# Solar_Tracker_2.net
KiCad netlist of a schematic drawn in Altium Designer
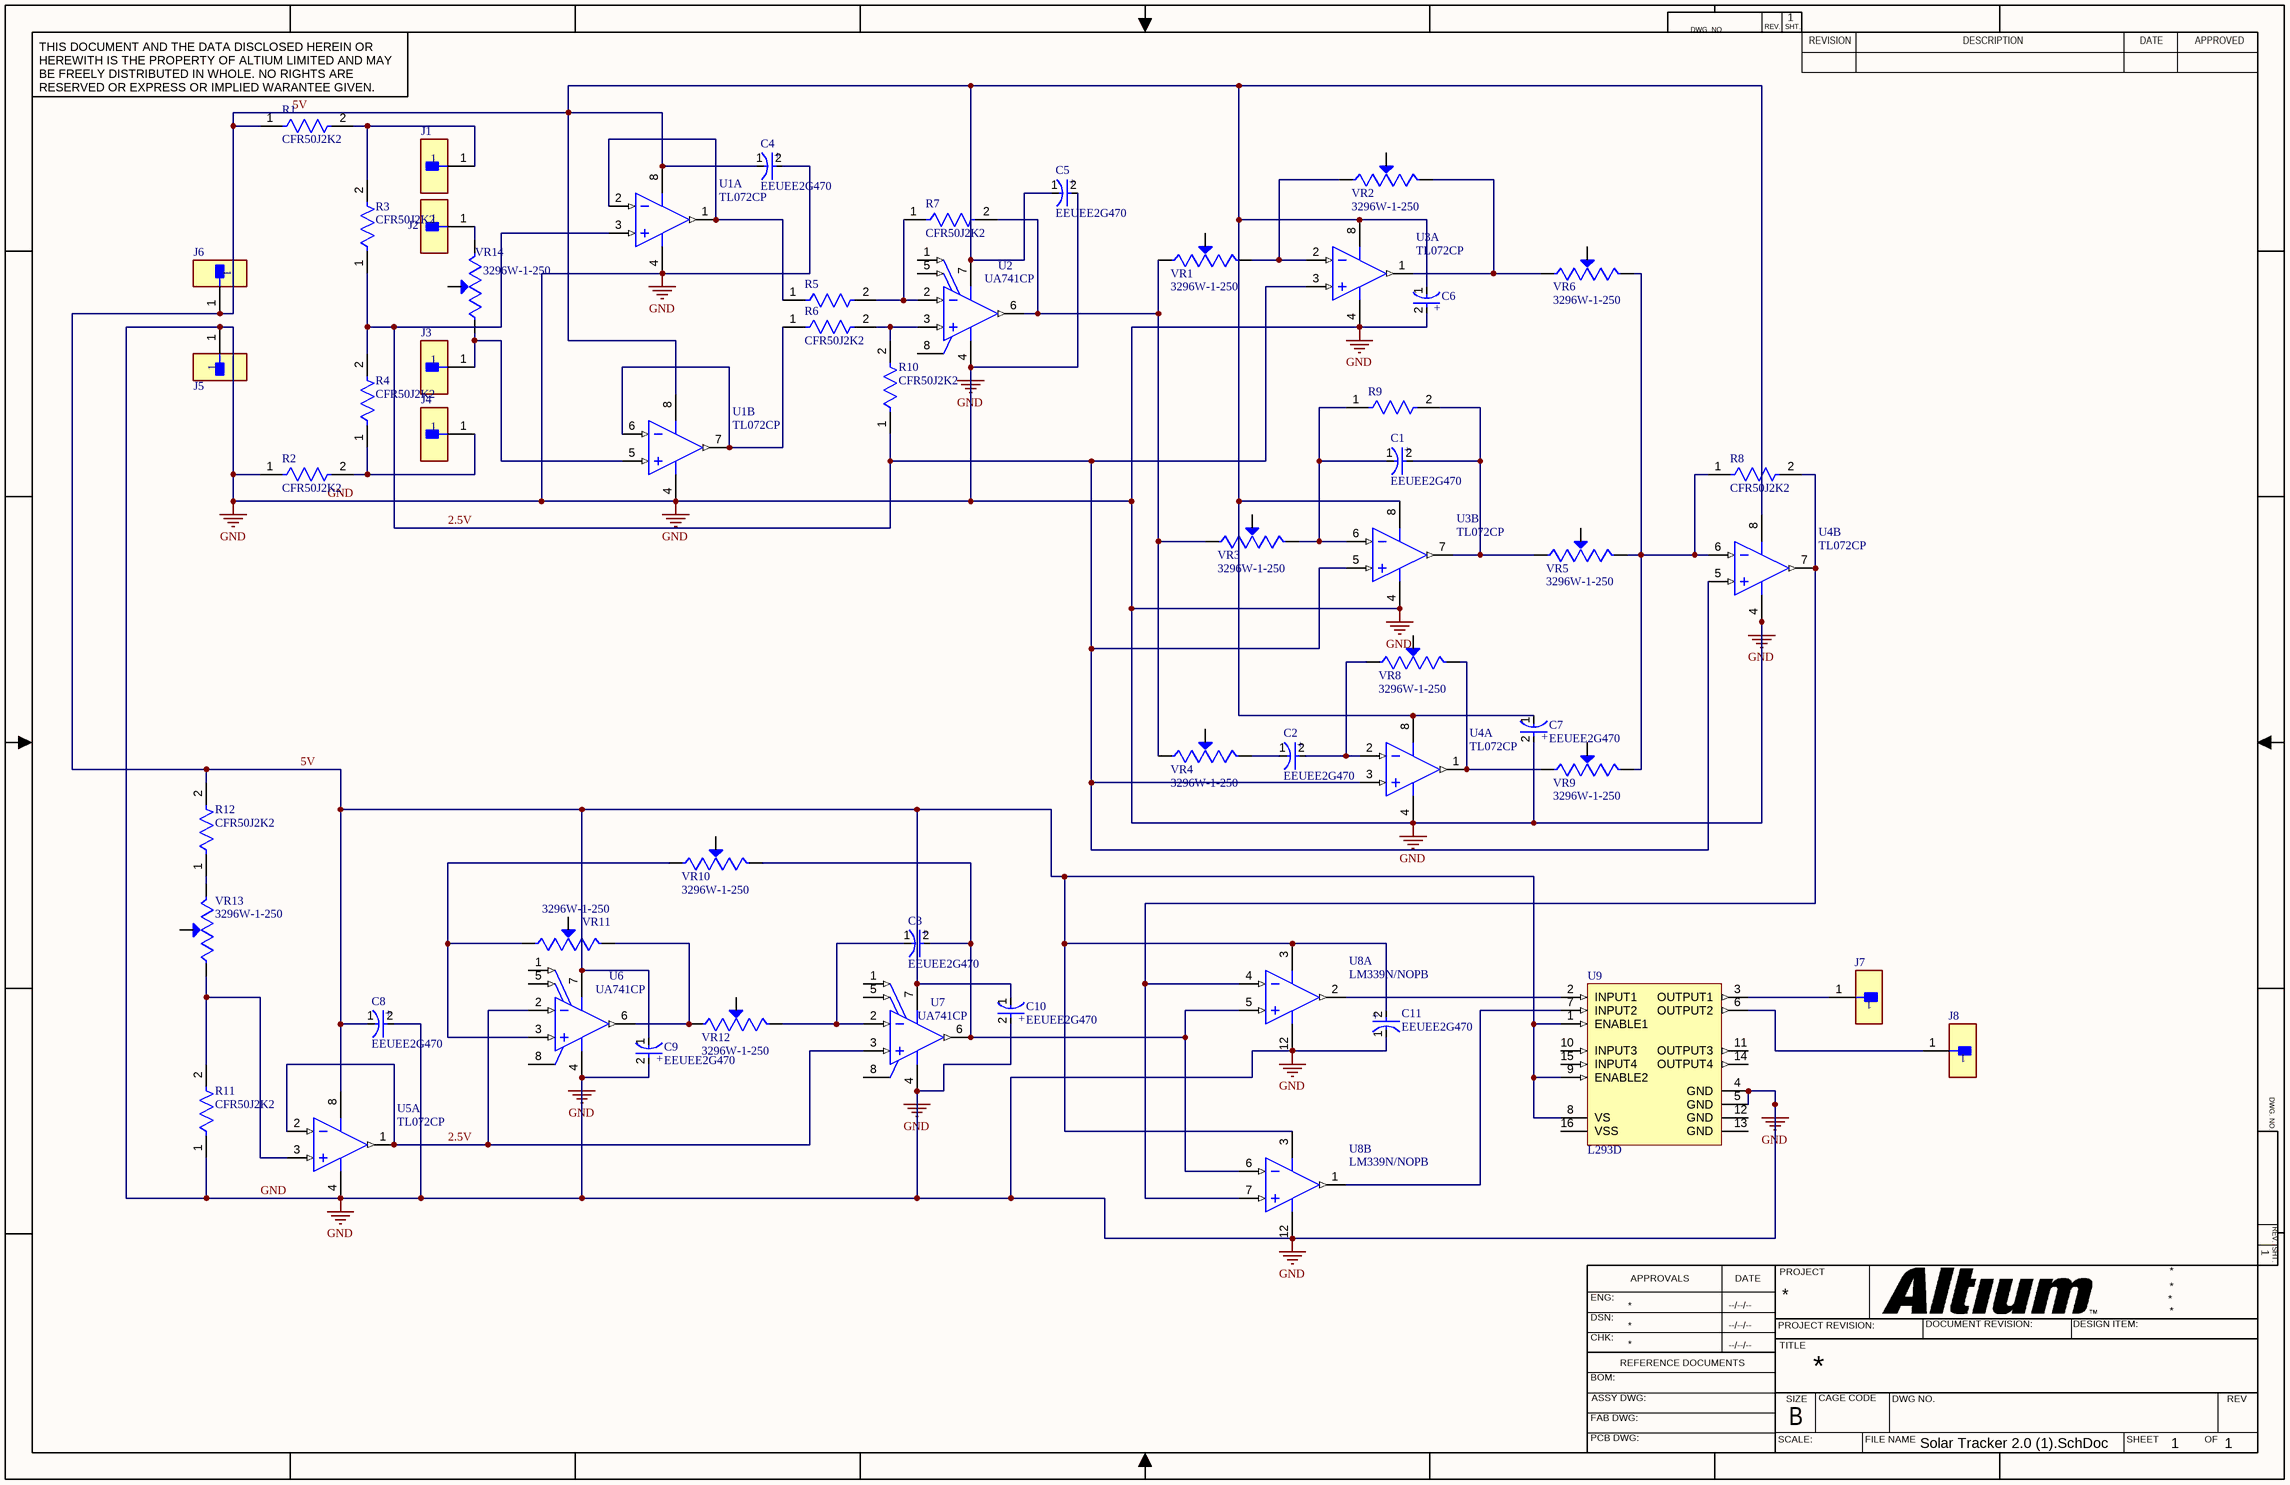
[diagram p0: Solar Tracker 2.0 (1).SchDoc]

(export (version "E")
  (design (tool "Eeschema 10.0.6"))
  (components
    (comp (ref "C1")
      (value "EEUEE2G470")
      (footprint "FP-RAD-TH-D_16_0_5-L_25_2-MFG")
      (description "Aluminum Electrolytic Capacitors (Radial Lead Type) 47uF ±20% 400V")
      (fields (field (name "VOLTAGE") "400V") (field (name "TOLERANCE") "20%"))
      (libsource (lib "Altium Content Vault") (part "203bc49f2ac43e59fd269a8c329ed05"))
    )
    (comp (ref "C2")
      (value "EEUEE2G470")
      (footprint "FP-RAD-TH-D_16_0_5-L_25_2-MFG")
      (description "Aluminum Electrolytic Capacitors (Radial Lead Type) 47uF ±20% 400V")
      (fields (field (name "VOLTAGE") "400V") (field (name "TOLERANCE") "20%"))
      (libsource (lib "Altium Content Vault") (part "203bc49f2ac43e59fd269a8c329ed05"))
    )
    (comp (ref "C3")
      (value "EEUEE2G470")
      (footprint "FP-RAD-TH-D_16_0_5-L_25_2-MFG")
      (description "Aluminum Electrolytic Capacitors (Radial Lead Type) 47uF ±20% 400V")
      (fields (field (name "VOLTAGE") "400V") (field (name "TOLERANCE") "20%"))
      (libsource (lib "Altium Content Vault") (part "203bc49f2ac43e59fd269a8c329ed05"))
    )
    (comp (ref "C4")
      (value "EEUEE2G470")
      (footprint "FP-RAD-TH-D_16_0_5-L_25_2-MFG")
      (description "Aluminum Electrolytic Capacitors (Radial Lead Type) 47uF ±20% 400V")
      (fields (field (name "VOLTAGE") "400V") (field (name "TOLERANCE") "20%"))
      (libsource (lib "Altium Content Vault") (part "203bc49f2ac43e59fd269a8c329ed05"))
    )
    (comp (ref "C5")
      (value "EEUEE2G470")
      (footprint "FP-RAD-TH-D_16_0_5-L_25_2-MFG")
      (description "Aluminum Electrolytic Capacitors (Radial Lead Type) 47uF ±20% 400V")
      (fields (field (name "VOLTAGE") "400V") (field (name "TOLERANCE") "20%"))
      (libsource (lib "Altium Content Vault") (part "203bc49f2ac43e59fd269a8c329ed05"))
    )
    (comp (ref "C6")
      (value "EEUEE2G470")
      (footprint "FP-RAD-TH-D_16_0_5-L_25_2-MFG")
      (description "Aluminum Electrolytic Capacitors (Radial Lead Type) 47uF ±20% 400V")
      (fields (field (name "VOLTAGE") "400V") (field (name "TOLERANCE") "20%"))
      (libsource (lib "Altium Content Vault") (part "203bc49f2ac43e59fd269a8c329ed05"))
    )
    (comp (ref "C7")
      (value "EEUEE2G470")
      (footprint "FP-RAD-TH-D_16_0_5-L_25_2-MFG")
      (description "Aluminum Electrolytic Capacitors (Radial Lead Type) 47uF ±20% 400V")
      (fields (field (name "VOLTAGE") "400V") (field (name "TOLERANCE") "20%"))
      (libsource (lib "Altium Content Vault") (part "203bc49f2ac43e59fd269a8c329ed05"))
    )
    (comp (ref "C8")
      (value "EEUEE2G470")
      (footprint "FP-RAD-TH-D_16_0_5-L_25_2-MFG")
      (description "Aluminum Electrolytic Capacitors (Radial Lead Type) 47uF ±20% 400V")
      (fields (field (name "VOLTAGE") "400V") (field (name "TOLERANCE") "20%"))
      (libsource (lib "Altium Content Vault") (part "203bc49f2ac43e59fd269a8c329ed05"))
    )
    (comp (ref "C9")
      (value "EEUEE2G470")
      (footprint "FP-RAD-TH-D_16_0_5-L_25_2-MFG")
      (description "Aluminum Electrolytic Capacitors (Radial Lead Type) 47uF ±20% 400V")
      (fields (field (name "VOLTAGE") "400V") (field (name "TOLERANCE") "20%"))
      (libsource (lib "Altium Content Vault") (part "203bc49f2ac43e59fd269a8c329ed05"))
    )
    (comp (ref "C10")
      (value "EEUEE2G470")
      (footprint "FP-RAD-TH-D_16_0_5-L_25_2-MFG")
      (description "Aluminum Electrolytic Capacitors (Radial Lead Type) 47uF ±20% 400V")
      (fields (field (name "VOLTAGE") "400V") (field (name "TOLERANCE") "20%"))
      (libsource (lib "Altium Content Vault") (part "203bc49f2ac43e59fd269a8c329ed05"))
    )
    (comp (ref "C11")
      (value "EEUEE2G470")
      (footprint "FP-RAD-TH-D_16_0_5-L_25_2-MFG")
      (description "Aluminum Electrolytic Capacitors (Radial Lead Type) 47uF ±20% 400V")
      (fields (field (name "VOLTAGE") "400V") (field (name "TOLERANCE") "20%"))
      (libsource (lib "Altium Content Vault") (part "203bc49f2ac43e59fd269a8c329ed05"))
    )
    (comp (ref "J1")
      (value "PBC01SAAN")
      (footprint "FP-PBC01SAAN-MFG")
      (description "CONN HEADER VERT 1POS")
      (libsource (lib "") (part "dd45045ce8184df9e99e12baf3f412c_2"))
    )
    (comp (ref "J2")
      (value "PBC01SAAN")
      (footprint "FP-PBC01SAAN-MFG")
      (description "CONN HEADER VERT 1POS")
      (libsource (lib "") (part "dd45045ce8184df9e99e12baf3f412c_2"))
    )
    (comp (ref "J3")
      (value "PBC01SAAN")
      (footprint "FP-PBC01SAAN-MFG")
      (description "CONN HEADER VERT 1POS")
      (libsource (lib "") (part "dd45045ce8184df9e99e12baf3f412c_2"))
    )
    (comp (ref "J4")
      (value "PBC01SAAN")
      (footprint "FP-PBC01SAAN-MFG")
      (description "CONN HEADER VERT 1POS")
      (libsource (lib "") (part "dd45045ce8184df9e99e12baf3f412c_2"))
    )
    (comp (ref "J5")
      (value "PBC01SAAN")
      (footprint "FP-PBC01SAAN-MFG")
      (description "CONN HEADER VERT 1POS")
      (libsource (lib "") (part "dd45045ce8184df9e99e12baf3f412c_1"))
    )
    (comp (ref "J6")
      (value "PBC01SAAN")
      (footprint "FP-PBC01SAAN-MFG")
      (description "CONN HEADER VERT 1POS")
      (libsource (lib "Altium Content Vault") (part "dd45045ce8184df9e99e12baf3f412c"))
    )
    (comp (ref "J7")
      (value "PBC01SAAN")
      (footprint "FP-PBC01SAAN-MFG")
      (description "CONN HEADER VERT 1POS")
      (libsource (lib "") (part "dd45045ce8184df9e99e12baf3f412c_3"))
    )
    (comp (ref "J8")
      (value "PBC01SAAN")
      (footprint "FP-PBC01SAAN-MFG")
      (description "CONN HEADER VERT 1POS")
      (libsource (lib "") (part "dd45045ce8184df9e99e12baf3f412c_3"))
    )
    (comp (ref "R1")
      (value "CFR50J2K2")
      (footprint "FP-CFR50J2K2-MFG")
      (description "RES 2.2K OHM 5% 1/2W AXIAL")
      (fields (field (name "TOLERANCE") "5%"))
      (libsource (lib "Altium Content Vault") (part "1029c3af85768c4190bb7ad29bc67b5"))
    )
    (comp (ref "R2")
      (value "CFR50J2K2")
      (footprint "FP-CFR50J2K2-MFG")
      (description "RES 2.2K OHM 5% 1/2W AXIAL")
      (fields (field (name "TOLERANCE") "5%"))
      (libsource (lib "Altium Content Vault") (part "1029c3af85768c4190bb7ad29bc67b5"))
    )
    (comp (ref "R3")
      (value "CFR50J2K2")
      (footprint "FP-CFR50J2K2-MFG")
      (description "RES 2.2K OHM 5% 1/2W AXIAL")
      (fields (field (name "TOLERANCE") "5%"))
      (libsource (lib "Altium Content Vault") (part "1029c3af85768c4190bb7ad29bc67b5"))
    )
    (comp (ref "R4")
      (value "CFR50J2K2")
      (footprint "FP-CFR50J2K2-MFG")
      (description "RES 2.2K OHM 5% 1/2W AXIAL")
      (fields (field (name "TOLERANCE") "5%"))
      (libsource (lib "Altium Content Vault") (part "1029c3af85768c4190bb7ad29bc67b5"))
    )
    (comp (ref "R5")
      (value "CFR50J2K2")
      (footprint "FP-CFR50J2K2-MFG")
      (description "RES 2.2K OHM 5% 1/2W AXIAL")
      (fields (field (name "TOLERANCE") "5%"))
      (libsource (lib "Altium Content Vault") (part "1029c3af85768c4190bb7ad29bc67b5"))
    )
    (comp (ref "R6")
      (value "CFR50J2K2")
      (footprint "FP-CFR50J2K2-MFG")
      (description "RES 2.2K OHM 5% 1/2W AXIAL")
      (fields (field (name "TOLERANCE") "5%"))
      (libsource (lib "Altium Content Vault") (part "1029c3af85768c4190bb7ad29bc67b5"))
    )
    (comp (ref "R7")
      (value "CFR50J2K2")
      (footprint "FP-CFR50J2K2-MFG")
      (description "RES 2.2K OHM 5% 1/2W AXIAL")
      (fields (field (name "TOLERANCE") "5%"))
      (libsource (lib "Altium Content Vault") (part "1029c3af85768c4190bb7ad29bc67b5"))
    )
    (comp (ref "R8")
      (value "CFR50J2K2")
      (footprint "FP-CFR50J2K2-MFG")
      (description "RES 2.2K OHM 5% 1/2W AXIAL")
      (fields (field (name "TOLERANCE") "5%"))
      (libsource (lib "Altium Content Vault") (part "1029c3af85768c4190bb7ad29bc67b5"))
    )
    (comp (ref "R9")
      (value "CFR50J2K2")
      (footprint "FP-CFR50J2K2-MFG")
      (description "RES 2.2K OHM 5% 1/2W AXIAL")
      (fields (field (name "TOLERANCE") "5%"))
      (libsource (lib "Altium Content Vault") (part "1029c3af85768c4190bb7ad29bc67b5"))
    )
    (comp (ref "R10")
      (value "CFR50J2K2")
      (footprint "FP-CFR50J2K2-MFG")
      (description "RES 2.2K OHM 5% 1/2W AXIAL")
      (fields (field (name "TOLERANCE") "5%"))
      (libsource (lib "Altium Content Vault") (part "1029c3af85768c4190bb7ad29bc67b5"))
    )
    (comp (ref "R11")
      (value "CFR50J2K2")
      (footprint "FP-CFR50J2K2-MFG")
      (description "RES 2.2K OHM 5% 1/2W AXIAL")
      (fields (field (name "TOLERANCE") "5%"))
      (libsource (lib "Altium Content Vault") (part "1029c3af85768c4190bb7ad29bc67b5"))
    )
    (comp (ref "R12")
      (value "CFR50J2K2")
      (footprint "FP-CFR50J2K2-MFG")
      (description "RES 2.2K OHM 5% 1/2W AXIAL")
      (fields (field (name "TOLERANCE") "5%"))
      (libsource (lib "Altium Content Vault") (part "1029c3af85768c4190bb7ad29bc67b5"))
    )
    (comp (ref "U1")
      (value "TL072CP")
      (footprint "P0008A")
      (fields (field (name "MANUFACTURER") "Texas Instruments"))
      (libsource (lib "Altium Content Vault") (part "TI-AMP-D6-2-8_D"))
    )
    (comp (ref "U2")
      (value "UA741CP")
      (footprint "P0008A")
      (description "General-Purpose Operational Amplifier, 7 to 36 V, 0 to 70 degC, 8-pin DIP (P8), Pb-Free (RoHS)")
      (fields (field (name "MANUFACTURER") "Texas Instruments"))
      (libsource (lib "Altium Content Vault") (part "TI-AMP-S5-2-8"))
    )
    (comp (ref "U3")
      (value "TL072CP")
      (footprint "P0008A")
      (fields (field (name "MANUFACTURER") "Texas Instruments"))
      (libsource (lib "Altium Content Vault") (part "TI-AMP-D6-2-8_D"))
    )
    (comp (ref "U4")
      (value "TL072CP")
      (footprint "P0008A")
      (fields (field (name "MANUFACTURER") "Texas Instruments"))
      (libsource (lib "Altium Content Vault") (part "TI-AMP-D6-2-8_D"))
    )
    (comp (ref "U5")
      (value "TL072CP")
      (footprint "P0008A")
      (fields (field (name "MANUFACTURER") "Texas Instruments"))
      (libsource (lib "Altium Content Vault") (part "TI-AMP-D6-2-8_D"))
    )
    (comp (ref "U6")
      (value "UA741CP")
      (footprint "P0008A")
      (description "General-Purpose Operational Amplifier, 7 to 36 V, 0 to 70 degC, 8-pin DIP (P8), Pb-Free (RoHS)")
      (fields (field (name "MANUFACTURER") "Texas Instruments"))
      (libsource (lib "Altium Content Vault") (part "TI-AMP-S5-2-8"))
    )
    (comp (ref "U7")
      (value "UA741CP")
      (footprint "P0008A")
      (description "General-Purpose Operational Amplifier, 7 to 36 V, 0 to 70 degC, 8-pin DIP (P8), Pb-Free (RoHS)")
      (fields (field (name "MANUFACTURER") "Texas Instruments"))
      (libsource (lib "Altium Content Vault") (part "TI-AMP-S5-2-8"))
    )
    (comp (ref "U8")
      (value "LM339N/NOPB")
      (footprint "NFF0014A")
      (description "Low Power Low Offset Voltage Quad Comparator, 14-pin MDIP, Pb-Free")
      (fields (field (name "MANUFACTURER") "Texas Instruments"))
      (libsource (lib "Altium Content Vault") (part "AN-COMP-LM139-14"))
    )
    (comp (ref "U9")
      (value "L293D")
      (footprint "STM-L293D-16")
      (description "Push-Pull Four Channel Driver with Diode, 4.5 to 36 V, -40 to 150 degC, 16-Pin PDIP, RoHS, Tube")
      (fields (field (name "MANUFACTURER") "STMicroelectronics"))
      (libsource (lib "Altium Content Vault") (part "STM-L293D-16"))
    )
    (comp (ref "VR1")
      (value "3296W-1-250")
      (footprint "TRIM_3296W-1-250")
      (description "25 Ohms 0.5W, 1/2W PC Pins Through Hole Trimmer Potentiometer Cermet 25.0 Turn Top Adjustment")
      (fields (field (name "MF") "Bourns"))
      (libsource (lib "3296W-1-250") (part "3296W-1-250"))
    )
    (comp (ref "VR2")
      (value "3296W-1-250")
      (footprint "TRIM_3296W-1-250")
      (description "25 Ohms 0.5W, 1/2W PC Pins Through Hole Trimmer Potentiometer Cermet 25.0 Turn Top Adjustment")
      (fields (field (name "MF") "Bourns"))
      (libsource (lib "3296W-1-250") (part "3296W-1-250"))
    )
    (comp (ref "VR3")
      (value "3296W-1-250")
      (footprint "TRIM_3296W-1-250")
      (description "25 Ohms 0.5W, 1/2W PC Pins Through Hole Trimmer Potentiometer Cermet 25.0 Turn Top Adjustment")
      (fields (field (name "MF") "Bourns"))
      (libsource (lib "3296W-1-250") (part "3296W-1-250"))
    )
    (comp (ref "VR4")
      (value "3296W-1-250")
      (footprint "TRIM_3296W-1-250")
      (description "25 Ohms 0.5W, 1/2W PC Pins Through Hole Trimmer Potentiometer Cermet 25.0 Turn Top Adjustment")
      (fields (field (name "MF") "Bourns"))
      (libsource (lib "3296W-1-250") (part "3296W-1-250"))
    )
    (comp (ref "VR5")
      (value "3296W-1-250")
      (footprint "TRIM_3296W-1-250")
      (description "25 Ohms 0.5W, 1/2W PC Pins Through Hole Trimmer Potentiometer Cermet 25.0 Turn Top Adjustment")
      (fields (field (name "MF") "Bourns"))
      (libsource (lib "3296W-1-250") (part "3296W-1-250"))
    )
    (comp (ref "VR6")
      (value "3296W-1-250")
      (footprint "TRIM_3296W-1-250")
      (description "25 Ohms 0.5W, 1/2W PC Pins Through Hole Trimmer Potentiometer Cermet 25.0 Turn Top Adjustment")
      (fields (field (name "MF") "Bourns"))
      (libsource (lib "3296W-1-250") (part "3296W-1-250"))
    )
    (comp (ref "VR8")
      (value "3296W-1-250")
      (footprint "TRIM_3296W-1-250")
      (description "25 Ohms 0.5W, 1/2W PC Pins Through Hole Trimmer Potentiometer Cermet 25.0 Turn Top Adjustment")
      (fields (field (name "MF") "Bourns"))
      (libsource (lib "3296W-1-250") (part "3296W-1-250"))
    )
    (comp (ref "VR9")
      (value "3296W-1-250")
      (footprint "TRIM_3296W-1-250")
      (description "25 Ohms 0.5W, 1/2W PC Pins Through Hole Trimmer Potentiometer Cermet 25.0 Turn Top Adjustment")
      (fields (field (name "MF") "Bourns"))
      (libsource (lib "3296W-1-250") (part "3296W-1-250"))
    )
    (comp (ref "VR10")
      (value "3296W-1-250")
      (footprint "TRIM_3296W-1-250")
      (description "25 Ohms 0.5W, 1/2W PC Pins Through Hole Trimmer Potentiometer Cermet 25.0 Turn Top Adjustment")
      (fields (field (name "MF") "Bourns"))
      (libsource (lib "3296W-1-250") (part "3296W-1-250"))
    )
    (comp (ref "VR11")
      (value "3296W-1-250")
      (footprint "TRIM_3296W-1-250")
      (description "25 Ohms 0.5W, 1/2W PC Pins Through Hole Trimmer Potentiometer Cermet 25.0 Turn Top Adjustment")
      (fields (field (name "MF") "Bourns"))
      (libsource (lib "3296W-1-250") (part "3296W-1-250"))
    )
    (comp (ref "VR12")
      (value "3296W-1-250")
      (footprint "TRIM_3296W-1-250")
      (description "25 Ohms 0.5W, 1/2W PC Pins Through Hole Trimmer Potentiometer Cermet 25.0 Turn Top Adjustment")
      (fields (field (name "MF") "Bourns"))
      (libsource (lib "3296W-1-250") (part "3296W-1-250"))
    )
    (comp (ref "VR13")
      (value "3296W-1-250")
      (footprint "TRIM_3296W-1-250")
      (description "25 Ohms 0.5W, 1/2W PC Pins Through Hole Trimmer Potentiometer Cermet 25.0 Turn Top Adjustment")
      (fields (field (name "MF") "Bourns"))
      (libsource (lib "3296W-1-250") (part "3296W-1-250"))
    )
    (comp (ref "VR14")
      (value "3296W-1-250")
      (footprint "TRIM_3296W-1-250")
      (description "25 Ohms 0.5W, 1/2W PC Pins Through Hole Trimmer Potentiometer Cermet 25.0 Turn Top Adjustment")
      (fields (field (name "MF") "Bourns"))
      (libsource (lib "3296W-1-250") (part "3296W-1-250"))
    )
  )
  (nets
    (net (code "1") (name "/2.5V") (class "Default")
      (node (ref "R10") (pin "1") (pinfunction "1_1") (pintype "passive"))
      (node (ref "R3") (pin "1") (pinfunction "1_1") (pintype "passive"))
      (node (ref "R4") (pin "2") (pinfunction "2_2") (pintype "passive"))
      (node (ref "U1") (pin "3") (pinfunction "IN1+_3") (pintype "input"))
      (node (ref "U3") (pin "3") (pinfunction "IN1+_3") (pintype "input"))
      (node (ref "U3") (pin "5") (pinfunction "IN2+_5") (pintype "input"))
      (node (ref "U4") (pin "3") (pinfunction "IN1+_3") (pintype "input"))
      (node (ref "U4") (pin "5") (pinfunction "IN2+_5") (pintype "input"))
      (node (ref "U5") (pin "1") (pinfunction "OUT1_1") (pintype "output"))
      (node (ref "U5") (pin "2") (pinfunction "IN1-_2") (pintype "input"))
      (node (ref "U6") (pin "2") (pinfunction "IN-_2") (pintype "input"))
      (node (ref "U7") (pin "3") (pinfunction "IN+_3") (pintype "input"))
    )
    (net (code "2") (name "/5V") (class "Default")
      (node (ref "C10") (pin "1") (pinfunction "C_1") (pintype "passive"))
      (node (ref "C11") (pin "2") (pinfunction "A_2") (pintype "passive"))
      (node (ref "C4") (pin "1") (pinfunction "C_1") (pintype "passive"))
      (node (ref "C5") (pin "1") (pinfunction "C_1") (pintype "passive"))
      (node (ref "C6") (pin "1") (pinfunction "C_1") (pintype "passive"))
      (node (ref "C7") (pin "1") (pinfunction "C_1") (pintype "passive"))
      (node (ref "C8") (pin "1") (pinfunction "C_1") (pintype "passive"))
      (node (ref "C9") (pin "1") (pinfunction "C_1") (pintype "passive"))
      (node (ref "J6") (pin "1") (pinfunction "1_1") (pintype "passive"))
      (node (ref "R1") (pin "1") (pinfunction "1_1") (pintype "passive"))
      (node (ref "R12") (pin "2") (pinfunction "2_2") (pintype "passive"))
      (node (ref "U1") (pin "8") (pinfunction "VCC+_8") (pintype "power_in"))
      (node (ref "U2") (pin "7") (pinfunction "VCC+_7") (pintype "power_in"))
      (node (ref "U3") (pin "8") (pinfunction "VCC+_8") (pintype "power_in"))
      (node (ref "U4") (pin "8") (pinfunction "VCC+_8") (pintype "power_in"))
      (node (ref "U5") (pin "8") (pinfunction "VCC+_8") (pintype "power_in"))
      (node (ref "U6") (pin "7") (pinfunction "VCC+_7") (pintype "power_in"))
      (node (ref "U7") (pin "7") (pinfunction "VCC+_7") (pintype "power_in"))
      (node (ref "U8") (pin "3") (pinfunction "V+_3") (pintype "power_in"))
      (node (ref "U9") (pin "1") (pinfunction "ENABLE1_1") (pintype "input"))
      (node (ref "U9") (pin "8") (pinfunction "VS_8") (pintype "power_in"))
      (node (ref "U9") (pin "9") (pinfunction "ENABLE2_9") (pintype "input"))
    )
    (net (code "3") (name "GND") (class "Default")
      (node (ref "C10") (pin "2") (pinfunction "A_2") (pintype "passive"))
      (node (ref "C11") (pin "1") (pinfunction "C_1") (pintype "passive"))
      (node (ref "C4") (pin "2") (pinfunction "A_2") (pintype "passive"))
      (node (ref "C5") (pin "2") (pinfunction "A_2") (pintype "passive"))
      (node (ref "C6") (pin "2") (pinfunction "A_2") (pintype "passive"))
      (node (ref "C7") (pin "2") (pinfunction "A_2") (pintype "passive"))
      (node (ref "C8") (pin "2") (pinfunction "A_2") (pintype "passive"))
      (node (ref "C9") (pin "2") (pinfunction "A_2") (pintype "passive"))
      (node (ref "J5") (pin "1") (pinfunction "1_1") (pintype "passive"))
      (node (ref "R11") (pin "1") (pinfunction "1_1") (pintype "passive"))
      (node (ref "R2") (pin "1") (pinfunction "1_1") (pintype "passive"))
      (node (ref "U1") (pin "4") (pinfunction "VCC-_4") (pintype "power_in"))
      (node (ref "U2") (pin "4") (pinfunction "VCC-_4") (pintype "power_in"))
      (node (ref "U3") (pin "4") (pinfunction "VCC-_4") (pintype "power_in"))
      (node (ref "U4") (pin "4") (pinfunction "VCC-_4") (pintype "power_in"))
      (node (ref "U5") (pin "4") (pinfunction "VCC-_4") (pintype "power_in"))
      (node (ref "U6") (pin "4") (pinfunction "VCC-_4") (pintype "power_in"))
      (node (ref "U7") (pin "4") (pinfunction "VCC-_4") (pintype "power_in"))
      (node (ref "U8") (pin "12") (pinfunction "GND_12") (pintype "power_in"))
      (node (ref "U9") (pin "4") (pinfunction "GND_4") (pintype "power_in"))
      (node (ref "U9") (pin "5") (pinfunction "GND_5") (pintype "power_in"))
    )
    (net (code "4") (name "Net-(C1-A)") (class "Default")
      (node (ref "C1") (pin "2") (pinfunction "A_2") (pintype "passive"))
      (node (ref "R9") (pin "2") (pinfunction "2_2") (pintype "passive"))
      (node (ref "U3") (pin "7") (pinfunction "OUT2_7") (pintype "output"))
      (node (ref "VR5") (pin "1") (pinfunction "CCW_1") (pintype "passive"))
    )
    (net (code "5") (name "Net-(C1-C)") (class "Default")
      (node (ref "C1") (pin "1") (pinfunction "C_1") (pintype "passive"))
      (node (ref "R9") (pin "1") (pinfunction "1_1") (pintype "passive"))
      (node (ref "U3") (pin "6") (pinfunction "IN2-_6") (pintype "input"))
      (node (ref "VR3") (pin "3") (pinfunction "CW_3") (pintype "passive"))
    )
    (net (code "6") (name "Net-(C2-A)") (class "Default")
      (node (ref "C2") (pin "2") (pinfunction "A_2") (pintype "passive"))
      (node (ref "U4") (pin "2") (pinfunction "IN1-_2") (pintype "input"))
      (node (ref "VR8") (pin "1") (pinfunction "CCW_1") (pintype "passive"))
    )
    (net (code "7") (name "Net-(C2-C)") (class "Default")
      (node (ref "C2") (pin "1") (pinfunction "C_1") (pintype "passive"))
      (node (ref "VR4") (pin "3") (pinfunction "CW_3") (pintype "passive"))
    )
    (net (code "8") (name "Net-(C3-A)") (class "Default")
      (node (ref "C3") (pin "2") (pinfunction "A_2") (pintype "passive"))
      (node (ref "U7") (pin "6") (pinfunction "OUT_6") (pintype "output"))
      (node (ref "U8") (pin "5") (pinfunction "IN1+_5") (pintype "input"))
      (node (ref "U8") (pin "6") (pinfunction "IN2-_6") (pintype "input"))
      (node (ref "VR10") (pin "3") (pinfunction "CW_3") (pintype "passive"))
    )
    (net (code "9") (name "Net-(C3-C)") (class "Default")
      (node (ref "C3") (pin "1") (pinfunction "C_1") (pintype "passive"))
      (node (ref "U7") (pin "2") (pinfunction "IN-_2") (pintype "input"))
      (node (ref "VR12") (pin "3") (pinfunction "CW_3") (pintype "passive"))
    )
    (net (code "10") (name "Net-(J1-Pad1)") (class "Default")
      (node (ref "J1") (pin "1") (pinfunction "1_1") (pintype "passive"))
      (node (ref "R1") (pin "2") (pinfunction "2_2") (pintype "passive"))
      (node (ref "R3") (pin "2") (pinfunction "2_2") (pintype "passive"))
    )
    (net (code "11") (name "Net-(J4-Pad1)") (class "Default")
      (node (ref "J4") (pin "1") (pinfunction "1_1") (pintype "passive"))
      (node (ref "R2") (pin "2") (pinfunction "2_2") (pintype "passive"))
      (node (ref "R4") (pin "1") (pinfunction "1_1") (pintype "passive"))
    )
    (net (code "12") (name "Net-(U1A-IN1-)") (class "Default")
      (node (ref "R5") (pin "1") (pinfunction "1_1") (pintype "passive"))
      (node (ref "U1") (pin "1") (pinfunction "OUT1_1") (pintype "output"))
      (node (ref "U1") (pin "2") (pinfunction "IN1-_2") (pintype "input"))
    )
    (net (code "13") (name "Net-(U1B-IN2+)") (class "Default")
      (node (ref "J3") (pin "1") (pinfunction "1_1") (pintype "passive"))
      (node (ref "U1") (pin "5") (pinfunction "IN2+_5") (pintype "input"))
      (node (ref "VR14") (pin "1") (pinfunction "CCW_1") (pintype "passive"))
    )
    (net (code "14") (name "Net-(U1B-IN2-)") (class "Default")
      (node (ref "R6") (pin "1") (pinfunction "1_1") (pintype "passive"))
      (node (ref "U1") (pin "6") (pinfunction "IN2-_6") (pintype "input"))
      (node (ref "U1") (pin "7") (pinfunction "OUT2_7") (pintype "output"))
    )
    (net (code "15") (name "Net-(U2-IN+)") (class "Default")
      (node (ref "R10") (pin "2") (pinfunction "2_2") (pintype "passive"))
      (node (ref "R6") (pin "2") (pinfunction "2_2") (pintype "passive"))
      (node (ref "U2") (pin "3") (pinfunction "IN+_3") (pintype "input"))
    )
    (net (code "16") (name "Net-(U2-IN-)") (class "Default")
      (node (ref "R5") (pin "2") (pinfunction "2_2") (pintype "passive"))
      (node (ref "R7") (pin "1") (pinfunction "1_1") (pintype "passive"))
      (node (ref "U2") (pin "2") (pinfunction "IN-_2") (pintype "input"))
    )
    (net (code "17") (name "Net-(U2-OUT)") (class "Default")
      (node (ref "R7") (pin "2") (pinfunction "2_2") (pintype "passive"))
      (node (ref "U2") (pin "6") (pinfunction "OUT_6") (pintype "output"))
      (node (ref "VR1") (pin "1") (pinfunction "CCW_1") (pintype "passive"))
      (node (ref "VR3") (pin "1") (pinfunction "CCW_1") (pintype "passive"))
      (node (ref "VR4") (pin "1") (pinfunction "CCW_1") (pintype "passive"))
    )
    (net (code "18") (name "Net-(U3A-IN1-)") (class "Default")
      (node (ref "U3") (pin "2") (pinfunction "IN1-_2") (pintype "input"))
      (node (ref "VR1") (pin "3") (pinfunction "CW_3") (pintype "passive"))
      (node (ref "VR2") (pin "1") (pinfunction "CCW_1") (pintype "passive"))
    )
    (net (code "19") (name "Net-(U3A-OUT1)") (class "Default")
      (node (ref "U3") (pin "1") (pinfunction "OUT1_1") (pintype "output"))
      (node (ref "VR2") (pin "3") (pinfunction "CW_3") (pintype "passive"))
      (node (ref "VR6") (pin "1") (pinfunction "CCW_1") (pintype "passive"))
    )
    (net (code "20") (name "Net-(U4A-OUT1)") (class "Default")
      (node (ref "U4") (pin "1") (pinfunction "OUT1_1") (pintype "output"))
      (node (ref "VR8") (pin "3") (pinfunction "CW_3") (pintype "passive"))
      (node (ref "VR9") (pin "1") (pinfunction "CCW_1") (pintype "passive"))
    )
    (net (code "21") (name "Net-(U4B-IN2-)") (class "Default")
      (node (ref "R8") (pin "1") (pinfunction "1_1") (pintype "passive"))
      (node (ref "U4") (pin "6") (pinfunction "IN2-_6") (pintype "input"))
      (node (ref "VR5") (pin "3") (pinfunction "CW_3") (pintype "passive"))
      (node (ref "VR6") (pin "3") (pinfunction "CW_3") (pintype "passive"))
      (node (ref "VR9") (pin "3") (pinfunction "CW_3") (pintype "passive"))
    )
    (net (code "22") (name "Net-(U4B-OUT2)") (class "Default")
      (node (ref "R8") (pin "2") (pinfunction "2_2") (pintype "passive"))
      (node (ref "U4") (pin "7") (pinfunction "OUT2_7") (pintype "output"))
      (node (ref "U8") (pin "4") (pinfunction "IN1-_4") (pintype "input"))
      (node (ref "U8") (pin "7") (pinfunction "IN2+_7") (pintype "input"))
    )
    (net (code "23") (name "Net-(U5A-IN1+)") (class "Default")
      (node (ref "R11") (pin "2") (pinfunction "2_2") (pintype "passive"))
      (node (ref "U5") (pin "3") (pinfunction "IN1+_3") (pintype "input"))
      (node (ref "VR13") (pin "1") (pinfunction "CCW_1") (pintype "passive"))
    )
    (net (code "24") (name "Net-(U6-IN+)") (class "Default")
      (node (ref "U6") (pin "3") (pinfunction "IN+_3") (pintype "input"))
      (node (ref "VR10") (pin "1") (pinfunction "CCW_1") (pintype "passive"))
      (node (ref "VR11") (pin "1") (pinfunction "CCW_1") (pintype "passive"))
    )
    (net (code "25") (name "Net-(U6-OUT)") (class "Default")
      (node (ref "U6") (pin "6") (pinfunction "OUT_6") (pintype "output"))
      (node (ref "VR11") (pin "3") (pinfunction "CW_3") (pintype "passive"))
      (node (ref "VR12") (pin "1") (pinfunction "CCW_1") (pintype "passive"))
    )
    (net (code "26") (name "Net-(U8A-OUT1)") (class "Default")
      (node (ref "U8") (pin "2") (pinfunction "OUT1_2") (pintype "output"))
      (node (ref "U9") (pin "2") (pinfunction "INPUT1_2") (pintype "input"))
    )
    (net (code "27") (name "Net-(U8B-OUT2)") (class "Default")
      (node (ref "U8") (pin "1") (pinfunction "OUT2_1") (pintype "output"))
      (node (ref "U9") (pin "7") (pinfunction "INPUT2_7") (pintype "input"))
    )
    (net (code "28") (name "Net-(U9-OUTPUT1)") (class "Default")
      (node (ref "J7") (pin "1") (pinfunction "1_1") (pintype "passive"))
      (node (ref "U9") (pin "3") (pinfunction "OUTPUT1_3") (pintype "output"))
    )
    (net (code "29") (name "Net-(U9-OUTPUT2)") (class "Default")
      (node (ref "J8") (pin "1") (pinfunction "1_1") (pintype "passive"))
      (node (ref "U9") (pin "6") (pinfunction "OUTPUT2_6") (pintype "output"))
    )
    (net (code "30") (name "Net-(VR13-CW)") (class "Default")
      (node (ref "R12") (pin "1") (pinfunction "1_1") (pintype "passive"))
      (node (ref "VR13") (pin "3") (pinfunction "CW_3") (pintype "passive"))
    )
    (net (code "31") (name "Net-(VR14-CW)") (class "Default")
      (node (ref "J2") (pin "1") (pinfunction "1_1") (pintype "passive"))
      (node (ref "VR14") (pin "3") (pinfunction "CW_3") (pintype "passive"))
    )
    (net (code "32") (name "unconnected-(U2-NC-Pad8)") (class "Default")
      (node (ref "U2") (pin "8") (pinfunction "NC_8") (pintype "passive"))
    )
    (net (code "33") (name "unconnected-(U2-OFFSET_N1-Pad1)") (class "Default")
      (node (ref "U2") (pin "1") (pinfunction "OFFSET_N1_1") (pintype "input"))
    )
    (net (code "34") (name "unconnected-(U2-OFFSET_N2-Pad5)") (class "Default")
      (node (ref "U2") (pin "5") (pinfunction "OFFSET_N2_5") (pintype "input"))
    )
    (net (code "35") (name "unconnected-(U6-NC-Pad8)") (class "Default")
      (node (ref "U6") (pin "8") (pinfunction "NC_8") (pintype "passive"))
    )
    (net (code "36") (name "unconnected-(U6-OFFSET_N1-Pad1)") (class "Default")
      (node (ref "U6") (pin "1") (pinfunction "OFFSET_N1_1") (pintype "input"))
    )
    (net (code "37") (name "unconnected-(U6-OFFSET_N2-Pad5)") (class "Default")
      (node (ref "U6") (pin "5") (pinfunction "OFFSET_N2_5") (pintype "input"))
    )
    (net (code "38") (name "unconnected-(U7-NC-Pad8)") (class "Default")
      (node (ref "U7") (pin "8") (pinfunction "NC_8") (pintype "passive"))
    )
    (net (code "39") (name "unconnected-(U7-OFFSET_N1-Pad1)") (class "Default")
      (node (ref "U7") (pin "1") (pinfunction "OFFSET_N1_1") (pintype "input"))
    )
    (net (code "40") (name "unconnected-(U7-OFFSET_N2-Pad5)") (class "Default")
      (node (ref "U7") (pin "5") (pinfunction "OFFSET_N2_5") (pintype "input"))
    )
    (net (code "41") (name "unconnected-(U9-GND-Pad12)") (class "Default")
      (node (ref "U9") (pin "12") (pinfunction "GND_12") (pintype "power_in"))
    )
    (net (code "42") (name "unconnected-(U9-GND-Pad13)") (class "Default")
      (node (ref "U9") (pin "13") (pinfunction "GND_13") (pintype "power_in"))
    )
    (net (code "43") (name "unconnected-(U9-INPUT3-Pad10)") (class "Default")
      (node (ref "U9") (pin "10") (pinfunction "INPUT3_10") (pintype "input"))
    )
    (net (code "44") (name "unconnected-(U9-INPUT4-Pad15)") (class "Default")
      (node (ref "U9") (pin "15") (pinfunction "INPUT4_15") (pintype "input"))
    )
    (net (code "45") (name "unconnected-(U9-OUTPUT3-Pad11)") (class "Default")
      (node (ref "U9") (pin "11") (pinfunction "OUTPUT3_11") (pintype "output"))
    )
    (net (code "46") (name "unconnected-(U9-OUTPUT4-Pad14)") (class "Default")
      (node (ref "U9") (pin "14") (pinfunction "OUTPUT4_14") (pintype "output"))
    )
    (net (code "47") (name "unconnected-(U9-VSS-Pad16)") (class "Default")
      (node (ref "U9") (pin "16") (pinfunction "VSS_16") (pintype "power_in"))
    )
    (net (code "48") (name "unconnected-(VR1-WIPER-Pad2)") (class "Default")
      (node (ref "VR1") (pin "2") (pinfunction "WIPER_2") (pintype "passive"))
    )
    (net (code "49") (name "unconnected-(VR2-WIPER-Pad2)") (class "Default")
      (node (ref "VR2") (pin "2") (pinfunction "WIPER_2") (pintype "passive"))
    )
    (net (code "50") (name "unconnected-(VR3-WIPER-Pad2)") (class "Default")
      (node (ref "VR3") (pin "2") (pinfunction "WIPER_2") (pintype "passive"))
    )
    (net (code "51") (name "unconnected-(VR4-WIPER-Pad2)") (class "Default")
      (node (ref "VR4") (pin "2") (pinfunction "WIPER_2") (pintype "passive"))
    )
    (net (code "52") (name "unconnected-(VR5-WIPER-Pad2)") (class "Default")
      (node (ref "VR5") (pin "2") (pinfunction "WIPER_2") (pintype "passive"))
    )
    (net (code "53") (name "unconnected-(VR6-WIPER-Pad2)") (class "Default")
      (node (ref "VR6") (pin "2") (pinfunction "WIPER_2") (pintype "passive"))
    )
    (net (code "54") (name "unconnected-(VR8-WIPER-Pad2)") (class "Default")
      (node (ref "VR8") (pin "2") (pinfunction "WIPER_2") (pintype "passive"))
    )
    (net (code "55") (name "unconnected-(VR9-WIPER-Pad2)") (class "Default")
      (node (ref "VR9") (pin "2") (pinfunction "WIPER_2") (pintype "passive"))
    )
    (net (code "56") (name "unconnected-(VR10-WIPER-Pad2)") (class "Default")
      (node (ref "VR10") (pin "2") (pinfunction "WIPER_2") (pintype "passive"))
    )
    (net (code "57") (name "unconnected-(VR11-WIPER-Pad2)") (class "Default")
      (node (ref "VR11") (pin "2") (pinfunction "WIPER_2") (pintype "passive"))
    )
    (net (code "58") (name "unconnected-(VR12-WIPER-Pad2)") (class "Default")
      (node (ref "VR12") (pin "2") (pinfunction "WIPER_2") (pintype "passive"))
    )
    (net (code "59") (name "unconnected-(VR13-WIPER-Pad2)") (class "Default")
      (node (ref "VR13") (pin "2") (pinfunction "WIPER_2") (pintype "passive"))
    )
    (net (code "60") (name "unconnected-(VR14-WIPER-Pad2)") (class "Default")
      (node (ref "VR14") (pin "2") (pinfunction "WIPER_2") (pintype "passive"))
    )
  )
)
